# DivergentSignalOffset.net
KiCad netlist of a schematic drawn in Altium Designer
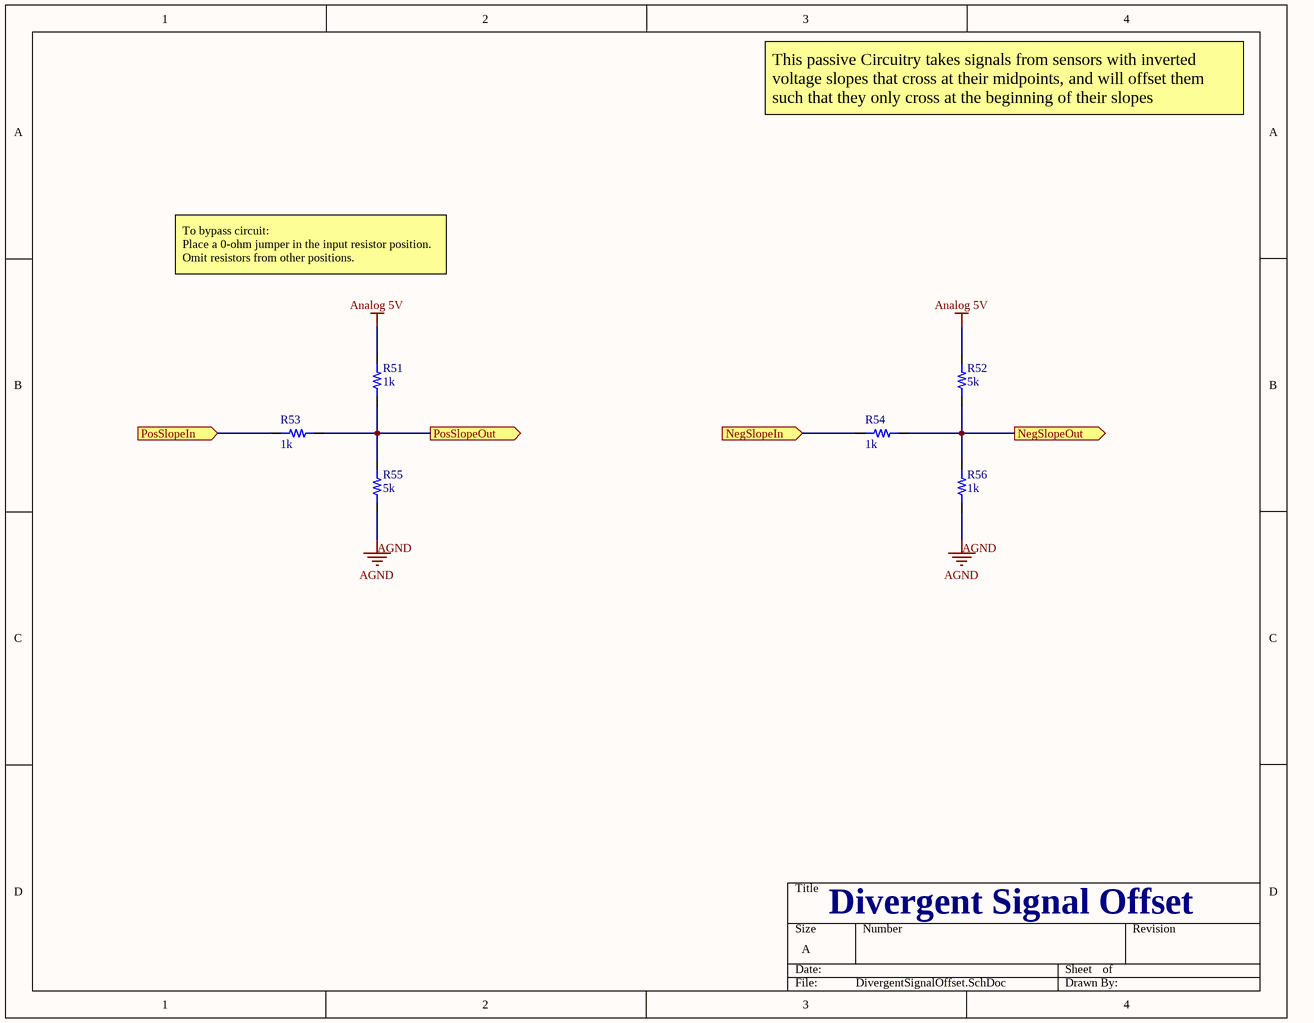
[diagram p0: DivergentSignalOffset.SchDoc]

(export (version "E")
  (design (tool "Eeschema 10.0.6"))
  (components
    (comp (ref "R51")
      (value "resistor")
      (footprint "0603")
      (fields (field (name "RESISTANCE") "1k"))
      (libsource (lib "altlib") (part "resistor"))
    )
    (comp (ref "R52")
      (value "resistor")
      (footprint "0603")
      (fields (field (name "RESISTANCE") "5k"))
      (libsource (lib "altlib") (part "resistor"))
    )
    (comp (ref "R53")
      (value "resistor")
      (footprint "0603")
      (fields (field (name "RESISTANCE") "1k"))
      (libsource (lib "altlib") (part "resistor"))
    )
    (comp (ref "R54")
      (value "resistor")
      (footprint "0603")
      (fields (field (name "RESISTANCE") "1k"))
      (libsource (lib "altlib") (part "resistor"))
    )
    (comp (ref "R55")
      (value "resistor")
      (footprint "0603")
      (fields (field (name "RESISTANCE") "5k"))
      (libsource (lib "altlib") (part "resistor"))
    )
    (comp (ref "R56")
      (value "resistor")
      (footprint "0603")
      (fields (field (name "RESISTANCE") "1k"))
      (libsource (lib "altlib") (part "resistor"))
    )
  )
  (nets
    (net (code "1") (name "/NegSlopeIn") (class "Default")
      (node (ref "R54") (pin "1") (pinfunction "1_1") (pintype "passive"))
    )
    (net (code "2") (name "/NegSlopeOut") (class "Default")
      (node (ref "R52") (pin "1") (pinfunction "1_1") (pintype "passive"))
      (node (ref "R54") (pin "2") (pinfunction "2_2") (pintype "passive"))
      (node (ref "R56") (pin "2") (pinfunction "2_2") (pintype "passive"))
    )
    (net (code "3") (name "/PosSlopeIn") (class "Default")
      (node (ref "R53") (pin "1") (pinfunction "1_1") (pintype "passive"))
    )
    (net (code "4") (name "/PosSlopeOut") (class "Default")
      (node (ref "R51") (pin "1") (pinfunction "1_1") (pintype "passive"))
      (node (ref "R53") (pin "2") (pinfunction "2_2") (pintype "passive"))
      (node (ref "R55") (pin "2") (pinfunction "2_2") (pintype "passive"))
    )
    (net (code "5") (name "AGND") (class "Default")
      (node (ref "R55") (pin "1") (pinfunction "1_1") (pintype "passive"))
      (node (ref "R56") (pin "1") (pinfunction "1_1") (pintype "passive"))
    )
    (net (code "6") (name "Analog 5V") (class "Default")
      (node (ref "R51") (pin "2") (pinfunction "2_2") (pintype "passive"))
      (node (ref "R52") (pin "2") (pinfunction "2_2") (pintype "passive"))
    )
  )
)
